# Power.net
KiCad netlist of a schematic drawn in Altium Designer
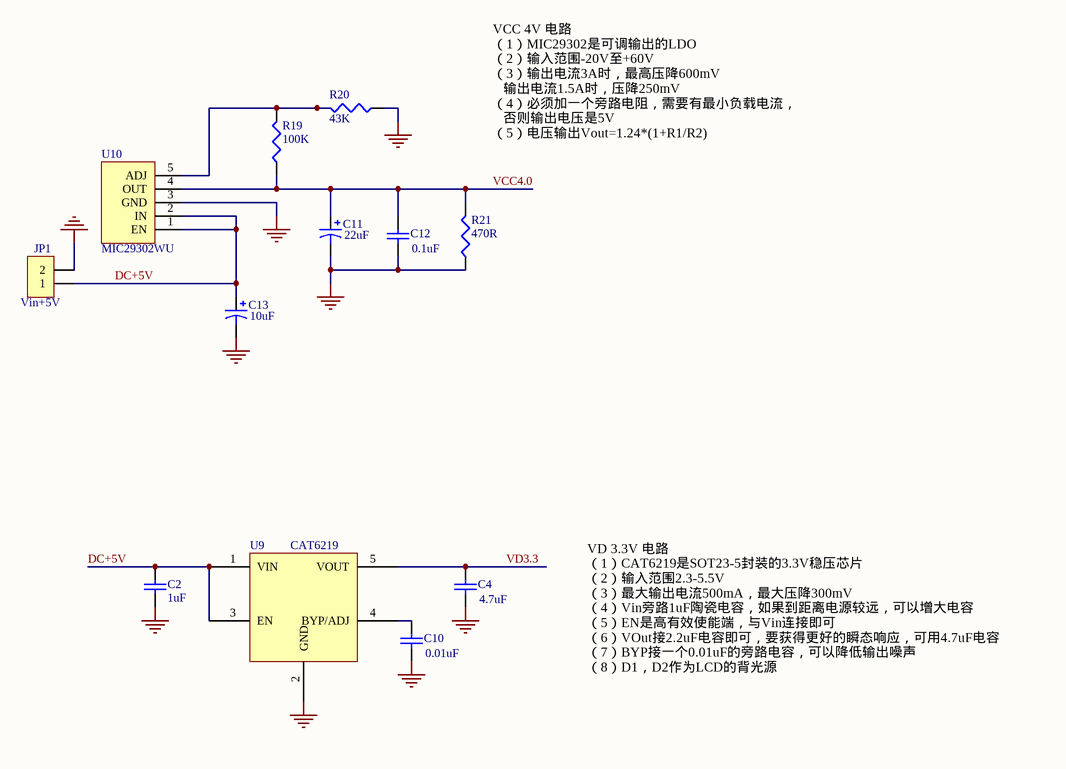
[diagram p0: Power.SchDoc]

(export (version "E")
  (design (tool "Eeschema 10.0.6"))
  (components
    (comp (ref "C2")
      (value "1uF")
      (footprint "1608[0603]")
      (description "Capacitor (Semiconductor SIM Model)")
      (fields (field (name "Comment") "Cap Semi") (field (name "PUBLISHER") "Altium Limited"))
      (libsource (lib "Miscellaneous Devices") (part "Cap Semi"))
    )
    (comp (ref "C4")
      (value "4.7uF")
      (footprint "1608[0603]")
      (description "Capacitor (Semiconductor SIM Model)")
      (fields (field (name "Comment") "Cap Semi") (field (name "PUBLISHER") "Altium Limited"))
      (libsource (lib "Miscellaneous Devices") (part "Cap Semi"))
    )
    (comp (ref "C10")
      (value "0.01uF")
      (footprint "1608[0603]")
      (description "Capacitor (Semiconductor SIM Model)")
      (fields (field (name "Comment") "Cap Semi") (field (name "PUBLISHER") "Altium Limited"))
      (libsource (lib "Miscellaneous Devices") (part "Cap Semi"))
    )
    (comp (ref "C11")
      (value "22uF")
      (footprint "C0805")
      (description "Polarized Capacitor (Surface Mount)")
      (fields (field (name "Comment") "Cap Pol3") (field (name "PUBLISHER") "Altium Limited"))
      (libsource (lib "Miscellaneous Devices") (part "Cap Pol3"))
    )
    (comp (ref "C12")
      (value "0.1uF")
      (footprint "1608[0603]")
      (description "Capacitor (Semiconductor SIM Model)")
      (fields (field (name "Comment") "Cap Semi") (field (name "PUBLISHER") "Altium Limited"))
      (libsource (lib "Miscellaneous Devices") (part "Cap Semi"))
    )
    (comp (ref "C13")
      (value "10uF")
      (footprint "C0805")
      (description "Polarized Capacitor (Surface Mount)")
      (fields (field (name "Comment") "Cap Pol3") (field (name "PUBLISHER") "Altium Limited"))
      (libsource (lib "Miscellaneous Devices") (part "Cap Pol3"))
    )
    (comp (ref "JP1")
      (value "Vin+5V")
      (footprint "XH2.54-2P")
      (description "2P接插件")
      (fields (field (name "版权归属") "源创客"))
      (libsource (lib "接插件") (part "Header 2"))
    )
    (comp (ref "R19")
      (value "100K")
      (footprint "J1-0603")
      (description "Resistor")
      (fields (field (name "Comment") "Res3") (field (name "PUBLISHER") "Altium Limited"))
      (libsource (lib "Miscellaneous Devices") (part "Res3"))
    )
    (comp (ref "R20")
      (value "43K")
      (footprint "J1-0603")
      (description "Resistor")
      (fields (field (name "Comment") "Res3") (field (name "PUBLISHER") "Altium Limited"))
      (libsource (lib "Miscellaneous Devices") (part "Res3"))
    )
    (comp (ref "R21")
      (value "470R")
      (footprint "J1-0603")
      (description "Resistor")
      (fields (field (name "Comment") "Res3") (field (name "PUBLISHER") "Altium Limited"))
      (libsource (lib "Miscellaneous Devices") (part "Res3"))
    )
    (comp (ref "U9")
      (value "CAT6219")
      (footprint "SOT23-5")
      (description "500 mA CMOS LDO Regulator")
      (libsource (lib "IC_电源") (part "CAT6219"))
    )
    (comp (ref "U10")
      (value "MIC29302WU")
      (footprint "TO263-5")
      (description "2A,  adjustable LDO")
      (libsource (lib "IC_电源") (part "MIC29302WU"))
    )
  )
  (nets
    (net (code "1") (name "/DC+5V") (class "Default")
      (node (ref "C13") (pin "1") (pinfunction "1_1") (pintype "passive"))
      (node (ref "C2") (pin "1") (pinfunction "1_1") (pintype "passive"))
      (node (ref "JP1") (pin "1") (pinfunction "1_1") (pintype "passive"))
      (node (ref "U10") (pin "1") (pinfunction "EN_1") (pintype "passive"))
      (node (ref "U10") (pin "2") (pinfunction "IN_2") (pintype "passive"))
      (node (ref "U9") (pin "1") (pinfunction "VIN_1") (pintype "passive"))
      (node (ref "U9") (pin "3") (pinfunction "EN_3") (pintype "passive"))
    )
    (net (code "2") (name "/VCC4.0") (class "Default")
      (node (ref "C11") (pin "1") (pinfunction "1_1") (pintype "passive"))
      (node (ref "C12") (pin "2") (pinfunction "2_2") (pintype "passive"))
      (node (ref "R19") (pin "1") (pinfunction "1_1") (pintype "passive"))
      (node (ref "R21") (pin "2") (pinfunction "2_2") (pintype "passive"))
      (node (ref "U10") (pin "4") (pinfunction "OUT_4") (pintype "passive"))
    )
    (net (code "3") (name "/VD3.3") (class "Default")
      (node (ref "C4") (pin "2") (pinfunction "2_2") (pintype "passive"))
      (node (ref "U9") (pin "5") (pinfunction "VOUT_5") (pintype "passive"))
    )
    (net (code "4") (name "GND") (class "Default")
      (node (ref "C10") (pin "1") (pinfunction "1_1") (pintype "passive"))
      (node (ref "C11") (pin "2") (pinfunction "2_2") (pintype "passive"))
      (node (ref "C12") (pin "1") (pinfunction "1_1") (pintype "passive"))
      (node (ref "C13") (pin "2") (pinfunction "2_2") (pintype "passive"))
      (node (ref "C2") (pin "2") (pinfunction "2_2") (pintype "passive"))
      (node (ref "C4") (pin "1") (pinfunction "1_1") (pintype "passive"))
      (node (ref "JP1") (pin "2") (pinfunction "2_2") (pintype "passive"))
      (node (ref "R20") (pin "1") (pinfunction "1_1") (pintype "passive"))
      (node (ref "R21") (pin "1") (pinfunction "1_1") (pintype "passive"))
      (node (ref "U10") (pin "3") (pinfunction "GND_3") (pintype "passive"))
      (node (ref "U9") (pin "2") (pinfunction "GND_2") (pintype "passive"))
    )
    (net (code "5") (name "Net-(U9-BYP{slash}ADJ)") (class "Default")
      (node (ref "C10") (pin "2") (pinfunction "2_2") (pintype "passive"))
      (node (ref "U9") (pin "4") (pinfunction "BYP/ADJ_4") (pintype "passive"))
    )
    (net (code "6") (name "Net-(U10-ADJ)") (class "Default")
      (node (ref "R19") (pin "2") (pinfunction "2_2") (pintype "passive"))
      (node (ref "R20") (pin "2") (pinfunction "2_2") (pintype "passive"))
      (node (ref "U10") (pin "5") (pinfunction "ADJ_5") (pintype "passive"))
    )
  )
)
